# EEPROM_AT24C512_SOP8.net
KiCad netlist of a schematic drawn in Altium Designer
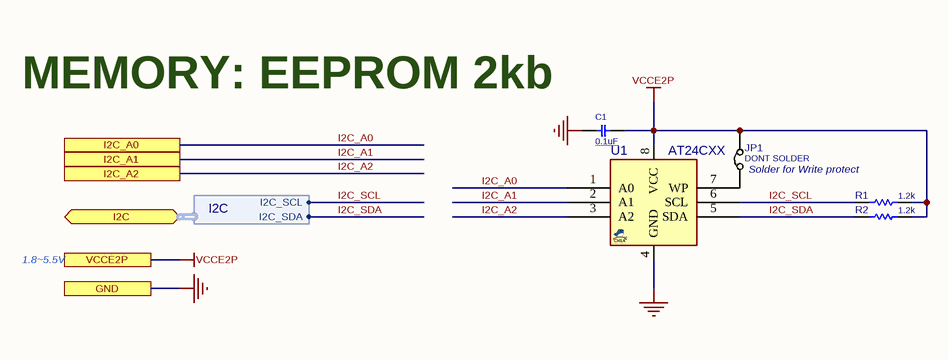
[diagram p0: EEPROM_AT24C512_SOP8.SchDoc]

(export (version "E")
  (design (tool "Eeschema 10.0.6"))
  (components
    (comp (ref "C1")
      (value "0.1uF")
      (footprint "C0402")
      (description "CAP, MLCC")
      (fields (field (name "MANF_P#") "MANF_PART#") (field (name "MANF") "Murata"))
      (libsource (lib "passive_smd") (part "CAP_SMD_MLCC"))
    )
    (comp (ref "JP1")
      (value "DONT SOLDER")
      (footprint "JP_60X100")
      (description "JUMPER,  solder")
      (fields (field (name "MANF") "MANF") (field (name "MANF_P#") "MANF_P#"))
      (libsource (lib "test-tp_jumper") (part "JUMPER_SOLDER"))
    )
    (comp (ref "R1")
      (value "1.2k")
      (footprint "R0402")
      (description "RESISTOR, SMD")
      (libsource (lib "passive_smd") (part "RES_SMD"))
    )
    (comp (ref "R2")
      (value "1.2k")
      (footprint "R0402")
      (description "RESISTOR, SMD")
      (libsource (lib "passive_smd") (part "RES_SMD"))
    )
    (comp (ref "U1")
      (value "AT24CXX")
      (footprint "SO_8")
      (description "EEPROM, I2C,")
      (libsource (lib "memory_eeprom_I2C") (part "EEPROM_I2C_AT24CXX_SOP8"))
    )
  )
  (nets
    (net (code "2") (name "/I2C_A0") (class "Default")
      (node (ref "U1") (pin "1") (pinfunction "A0_1") (pintype "passive"))
    )
    (net (code "3") (name "/I2C_A1") (class "Default")
      (node (ref "U1") (pin "2") (pinfunction "A1_2") (pintype "passive"))
    )
    (net (code "4") (name "/I2C_A2") (class "Default")
      (node (ref "U1") (pin "3") (pinfunction "A2_3") (pintype "passive"))
    )
    (net (code "5") (name "/I2C_SCL") (class "Default")
      (node (ref "R1") (pin "2") (pinfunction "2_2") (pintype "passive"))
      (node (ref "U1") (pin "6") (pinfunction "SCL_6") (pintype "passive"))
    )
    (net (code "6") (name "/I2C_SDA") (class "Default")
      (node (ref "R2") (pin "2") (pinfunction "2_2") (pintype "passive"))
      (node (ref "U1") (pin "5") (pinfunction "SDA_5") (pintype "passive"))
    )
    (net (code "8") (name "GND") (class "Default")
      (node (ref "C1") (pin "1") (pinfunction "1_1") (pintype "passive"))
      (node (ref "U1") (pin "4") (pinfunction "GND_4") (pintype "passive"))
    )
    (net (code "9") (name "Net-(U1-WP)") (class "Default")
      (node (ref "JP1") (pin "1") (pinfunction "1_1") (pintype "passive"))
      (node (ref "U1") (pin "7") (pinfunction "WP_7") (pintype "passive"))
    )
    (net (code "10") (name "VCCE2P") (class "Default")
      (node (ref "C1") (pin "2") (pinfunction "2_2") (pintype "passive"))
      (node (ref "JP1") (pin "2") (pinfunction "2_2") (pintype "passive"))
      (node (ref "R1") (pin "1") (pinfunction "1_1") (pintype "passive"))
      (node (ref "R2") (pin "1") (pinfunction "1_1") (pintype "passive"))
      (node (ref "U1") (pin "8") (pinfunction "VCC_8") (pintype "passive"))
    )
  )
)
